# Tugas_sensor_RizqullohFaathirAkmalY_2150.net
KiCad netlist of a schematic drawn in EAGLE
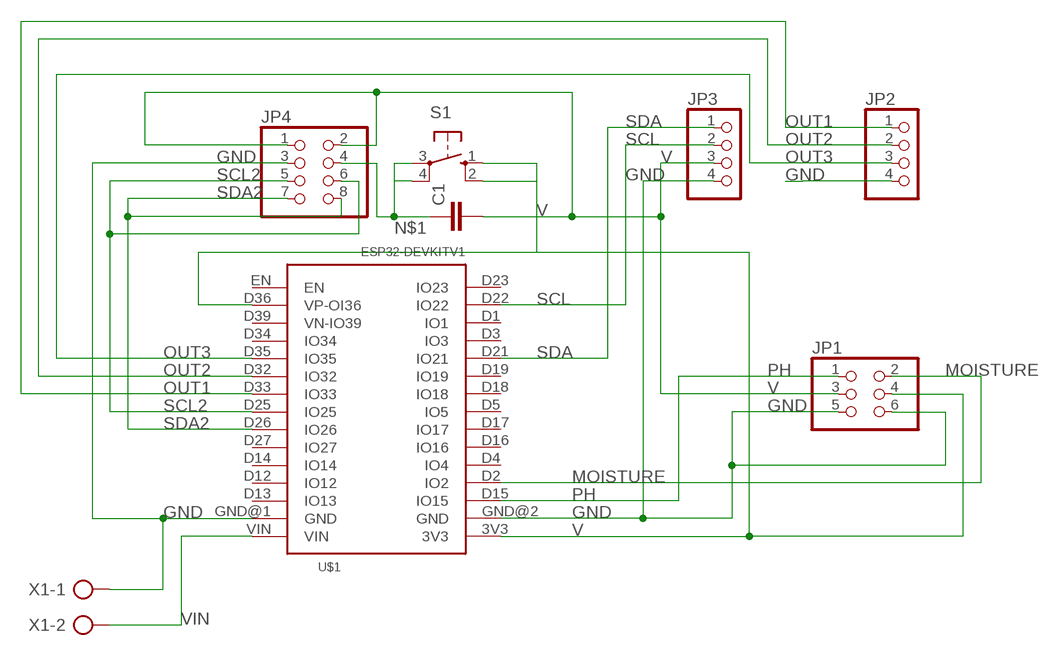
[diagram p0: schematic, sheet 1]

(export (version "E")
  (design (tool "Eeschema 10.0.6"))
  (components
    (comp (ref "C1")
      (value "C-EU050-030X075")
      (footprint "eagle-import:C050-030X075")
      (libsource (lib "eagle-import") (part "C-EU050-030X075"))
    )
    (comp (ref "JP1")
      (value "PINHD-2X3")
      (footprint "eagle-import:2X03")
      (libsource (lib "eagle-import") (part "PINHD-2X3"))
    )
    (comp (ref "JP2")
      (value "PINHD-1X4")
      (footprint "eagle-import:1X04")
      (libsource (lib "eagle-import") (part "PINHD-1X4"))
    )
    (comp (ref "JP3")
      (value "PINHD-1X4")
      (footprint "eagle-import:1X04")
      (libsource (lib "eagle-import") (part "PINHD-1X4"))
    )
    (comp (ref "JP4")
      (value "PINHD-2X4")
      (footprint "eagle-import:2X04")
      (libsource (lib "eagle-import") (part "PINHD-2X4"))
    )
    (comp (ref "S1")
      (value "10-XX")
      (footprint "eagle-import:B3F-10XX")
      (fields (field (name "MPN") "B3F-1000"))
      (libsource (lib "eagle-import") (part "10-XX"))
    )
    (comp (ref "U$1")
      (value "ESP32DEVKITV1")
      (footprint "eagle-import:ESP32-DEVKITV1")
      (libsource (lib "eagle-import") (part "ESP32DEVKITV1"))
    )
    (comp (ref "X1")
      (value "AK300/2")
      (footprint "eagle-import:AK300_2")
      (libsource (lib "eagle-import") (part "AK300/2"))
    )
  )
  (nets
    (net (code "1") (name "/GND") (class "Default")
      (node (ref "JP1") (pin "5") (pinfunction "5_5") (pintype "passive"))
      (node (ref "JP1") (pin "6") (pinfunction "6_6") (pintype "passive"))
      (node (ref "JP2") (pin "4") (pinfunction "4_4") (pintype "passive"))
      (node (ref "JP3") (pin "4") (pinfunction "4_4") (pintype "passive"))
      (node (ref "JP4") (pin "3") (pinfunction "3_3") (pintype "passive"))
      (node (ref "S1") (pin "4") (pinfunction "P1_4") (pintype "passive"))
      (node (ref "U$1") (pin "GND@1") (pinfunction "GND_GND@1") (pintype "bidirectional"))
      (node (ref "U$1") (pin "GND@2") (pinfunction "GND_GND@2") (pintype "bidirectional"))
      (node (ref "X1") (pin "1") (pinfunction "KL_1") (pintype "passive"))
    )
    (net (code "2") (name "/MOISTURE") (class "Default")
      (node (ref "JP1") (pin "2") (pinfunction "2_2") (pintype "passive"))
      (node (ref "U$1") (pin "D2") (pinfunction "IO2_D2") (pintype "bidirectional"))
    )
    (net (code "3") (name "/N$1") (class "Default")
      (node (ref "C1") (pin "1") (pinfunction "1_1") (pintype "passive"))
      (node (ref "JP4") (pin "4") (pinfunction "4_4") (pintype "passive"))
      (node (ref "S1") (pin "3") (pinfunction "P_3") (pintype "passive"))
    )
    (net (code "4") (name "/OUT1") (class "Default")
      (node (ref "JP2") (pin "1") (pinfunction "1_1") (pintype "passive"))
      (node (ref "U$1") (pin "D33") (pinfunction "IO33_D33") (pintype "bidirectional"))
    )
    (net (code "5") (name "/OUT2") (class "Default")
      (node (ref "JP2") (pin "2") (pinfunction "2_2") (pintype "passive"))
      (node (ref "U$1") (pin "D32") (pinfunction "IO32_D32") (pintype "bidirectional"))
    )
    (net (code "6") (name "/OUT3") (class "Default")
      (node (ref "JP2") (pin "3") (pinfunction "3_3") (pintype "passive"))
      (node (ref "U$1") (pin "D35") (pinfunction "IO35_D35") (pintype "bidirectional"))
    )
    (net (code "7") (name "/PH") (class "Default")
      (node (ref "JP1") (pin "1") (pinfunction "1_1") (pintype "passive"))
      (node (ref "U$1") (pin "D15") (pinfunction "IO15_D15") (pintype "bidirectional"))
    )
    (net (code "8") (name "/SCL") (class "Default")
      (node (ref "JP3") (pin "2") (pinfunction "2_2") (pintype "passive"))
      (node (ref "U$1") (pin "D22") (pinfunction "IO22_D22") (pintype "bidirectional"))
    )
    (net (code "9") (name "/SCL2") (class "Default")
      (node (ref "JP4") (pin "5") (pinfunction "5_5") (pintype "passive"))
      (node (ref "JP4") (pin "6") (pinfunction "6_6") (pintype "passive"))
      (node (ref "U$1") (pin "D25") (pinfunction "IO25_D25") (pintype "bidirectional"))
    )
    (net (code "10") (name "/SDA") (class "Default")
      (node (ref "JP3") (pin "1") (pinfunction "1_1") (pintype "passive"))
      (node (ref "U$1") (pin "D21") (pinfunction "IO21_D21") (pintype "bidirectional"))
    )
    (net (code "11") (name "/SDA2") (class "Default")
      (node (ref "JP4") (pin "7") (pinfunction "7_7") (pintype "passive"))
      (node (ref "JP4") (pin "8") (pinfunction "8_8") (pintype "passive"))
      (node (ref "U$1") (pin "D26") (pinfunction "IO26_D26") (pintype "bidirectional"))
    )
    (net (code "12") (name "/V") (class "Default")
      (node (ref "C1") (pin "2") (pinfunction "2_2") (pintype "passive"))
      (node (ref "JP1") (pin "3") (pinfunction "3_3") (pintype "passive"))
      (node (ref "JP1") (pin "4") (pinfunction "4_4") (pintype "passive"))
      (node (ref "JP3") (pin "3") (pinfunction "3_3") (pintype "passive"))
      (node (ref "JP4") (pin "1") (pinfunction "1_1") (pintype "passive"))
      (node (ref "JP4") (pin "2") (pinfunction "2_2") (pintype "passive"))
      (node (ref "S1") (pin "1") (pinfunction "S_1") (pintype "passive"))
      (node (ref "S1") (pin "2") (pinfunction "S1_2") (pintype "passive"))
      (node (ref "U$1") (pin "3V3") (pinfunction "3V3_3V3") (pintype "bidirectional"))
      (node (ref "U$1") (pin "D36") (pinfunction "VP-OI36_D36") (pintype "bidirectional"))
    )
    (net (code "13") (name "/VIN") (class "Default")
      (node (ref "U$1") (pin "VIN") (pinfunction "VIN_VIN") (pintype "bidirectional"))
      (node (ref "X1") (pin "2") (pinfunction "KL_2") (pintype "passive"))
    )
    (net (code "14") (name "unconnected-(U$1-IO1-PadD1)") (class "Default")
      (node (ref "U$1") (pin "D1") (pinfunction "IO1_D1") (pintype "bidirectional"))
    )
    (net (code "15") (name "unconnected-(U$1-IO3-PadD3)") (class "Default")
      (node (ref "U$1") (pin "D3") (pinfunction "IO3_D3") (pintype "bidirectional"))
    )
    (net (code "16") (name "unconnected-(U$1-IO4-PadD4)") (class "Default")
      (node (ref "U$1") (pin "D4") (pinfunction "IO4_D4") (pintype "bidirectional"))
    )
    (net (code "17") (name "unconnected-(U$1-IO5-PadD5)") (class "Default")
      (node (ref "U$1") (pin "D5") (pinfunction "IO5_D5") (pintype "bidirectional"))
    )
    (net (code "18") (name "unconnected-(U$1-IO12-PadD12)") (class "Default")
      (node (ref "U$1") (pin "D12") (pinfunction "IO12_D12") (pintype "bidirectional"))
    )
    (net (code "19") (name "unconnected-(U$1-IO13-PadD13)") (class "Default")
      (node (ref "U$1") (pin "D13") (pinfunction "IO13_D13") (pintype "bidirectional"))
    )
    (net (code "20") (name "unconnected-(U$1-IO14-PadD14)") (class "Default")
      (node (ref "U$1") (pin "D14") (pinfunction "IO14_D14") (pintype "bidirectional"))
    )
    (net (code "21") (name "unconnected-(U$1-IO16-PadD16)") (class "Default")
      (node (ref "U$1") (pin "D16") (pinfunction "IO16_D16") (pintype "bidirectional"))
    )
    (net (code "22") (name "unconnected-(U$1-IO17-PadD17)") (class "Default")
      (node (ref "U$1") (pin "D17") (pinfunction "IO17_D17") (pintype "bidirectional"))
    )
    (net (code "23") (name "unconnected-(U$1-IO18-PadD18)") (class "Default")
      (node (ref "U$1") (pin "D18") (pinfunction "IO18_D18") (pintype "bidirectional"))
    )
    (net (code "24") (name "unconnected-(U$1-IO19-PadD19)") (class "Default")
      (node (ref "U$1") (pin "D19") (pinfunction "IO19_D19") (pintype "bidirectional"))
    )
    (net (code "25") (name "unconnected-(U$1-IO23-PadD23)") (class "Default")
      (node (ref "U$1") (pin "D23") (pinfunction "IO23_D23") (pintype "bidirectional"))
    )
    (net (code "26") (name "unconnected-(U$1-IO27-PadD27)") (class "Default")
      (node (ref "U$1") (pin "D27") (pinfunction "IO27_D27") (pintype "bidirectional"))
    )
    (net (code "27") (name "unconnected-(U$1-IO34-PadD34)") (class "Default")
      (node (ref "U$1") (pin "D34") (pinfunction "IO34_D34") (pintype "bidirectional"))
    )
    (net (code "28") (name "unconnected-(U$1-PadEN)") (class "Default")
      (node (ref "U$1") (pin "EN") (pinfunction "EN_EN") (pintype "bidirectional"))
    )
    (net (code "29") (name "unconnected-(U$1-VN-IO39-PadD39)") (class "Default")
      (node (ref "U$1") (pin "D39") (pinfunction "VN-IO39_D39") (pintype "bidirectional"))
    )
  )
)
